# TMP102_Breakout-v12.net
KiCad netlist of a schematic drawn in EAGLE
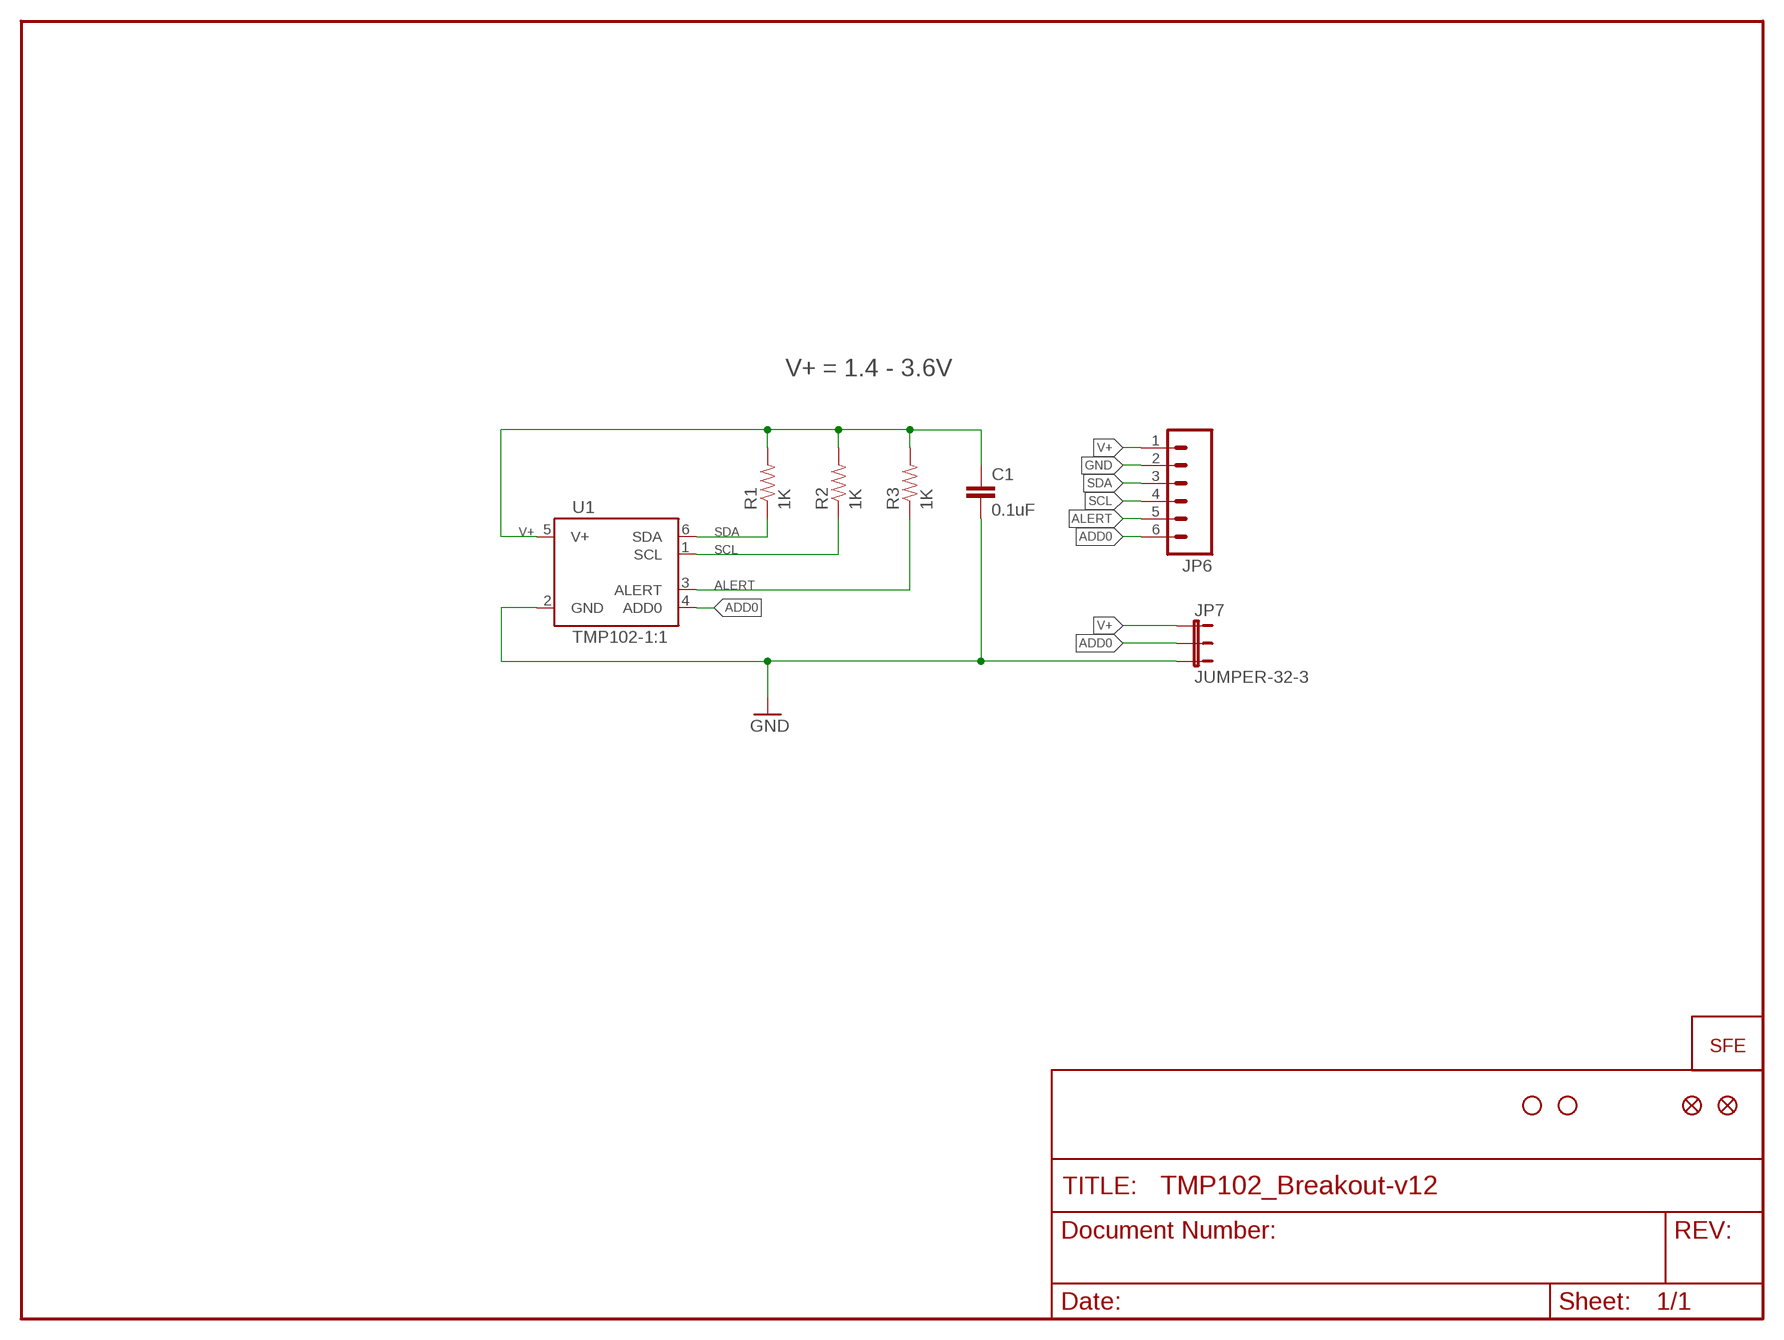
[diagram p0: schematic, sheet 1]

(export (version "E")
  (design (tool "Eeschema 10.0.6"))
  (components
    (comp (ref "C1")
      (value "0.1uF")
      (footprint "eagle-import:0603-CAP")
      (libsource (lib "eagle-import") (part "CAP0603-CAP"))
    )
    (comp (ref "JP1")
      (value "STAND-OFFTIGHT")
      (footprint "eagle-import:STAND-OFF-TIGHT")
      (libsource (lib "eagle-import") (part "STAND-OFFTIGHT"))
    )
    (comp (ref "JP2")
      (value "STAND-OFFTIGHT")
      (footprint "eagle-import:STAND-OFF-TIGHT")
      (libsource (lib "eagle-import") (part "STAND-OFFTIGHT"))
    )
    (comp (ref "JP3")
      (value "LOGO-SFESK")
      (footprint "eagle-import:SFE-LOGO-FLAME")
      (libsource (lib "eagle-import") (part "LOGO-SFESK"))
    )
    (comp (ref "JP4")
      (value "FIDUCIAL1X2")
      (footprint "eagle-import:FIDUCIAL-1X2")
      (libsource (lib "eagle-import") (part "FIDUCIAL1X2"))
    )
    (comp (ref "JP5")
      (value "FIDUCIAL1X2")
      (footprint "eagle-import:FIDUCIAL-1X2")
      (libsource (lib "eagle-import") (part "FIDUCIAL1X2"))
    )
    (comp (ref "JP6")
      (value "M06SIP")
      (footprint "eagle-import:1X06")
      (libsource (lib "eagle-import") (part "M06SIP"))
    )
    (comp (ref "JP7")
      (value "JUMPER-32-3")
      (footprint "eagle-import:SJ_3_PASTE2&3")
      (libsource (lib "eagle-import") (part "JUMPER-32-3"))
    )
    (comp (ref "R1")
      (value "1K")
      (footprint "eagle-import:0603-RES")
      (libsource (lib "eagle-import") (part "RESISTOR0603-RES"))
    )
    (comp (ref "R2")
      (value "1K")
      (footprint "eagle-import:0603-RES")
      (libsource (lib "eagle-import") (part "RESISTOR0603-RES"))
    )
    (comp (ref "R3")
      (value "1K")
      (footprint "eagle-import:0603-RES")
      (libsource (lib "eagle-import") (part "RESISTOR0603-RES"))
    )
    (comp (ref "U1")
      (value "TMP102-1:1")
      (footprint "eagle-import:SOT563-2")
      (libsource (lib "eagle-import") (part "TMP102-1{colon}1"))
    )
  )
  (nets
    (net (code "1") (name "ADD0") (class "Default")
      (node (ref "JP6") (pin "6") (pinfunction "6_6") (pintype "passive"))
      (node (ref "JP7") (pin "2") (pinfunction "2_2") (pintype "passive"))
      (node (ref "U1") (pin "4") (pinfunction "ADD0_4") (pintype "bidirectional"))
    )
    (net (code "2") (name "ALERT") (class "Default")
      (node (ref "JP6") (pin "5") (pinfunction "5_5") (pintype "passive"))
      (node (ref "R3") (pin "1") (pinfunction "1_1") (pintype "passive"))
      (node (ref "U1") (pin "3") (pinfunction "ALERT_3") (pintype "bidirectional"))
    )
    (net (code "3") (name "GND") (class "Default")
      (node (ref "C1") (pin "2") (pinfunction "2_2") (pintype "passive"))
      (node (ref "JP6") (pin "2") (pinfunction "2_2") (pintype "passive"))
      (node (ref "JP7") (pin "3") (pinfunction "3_3") (pintype "passive"))
      (node (ref "U1") (pin "2") (pinfunction "GND_2") (pintype "bidirectional"))
    )
    (net (code "4") (name "SCL") (class "Default")
      (node (ref "JP6") (pin "4") (pinfunction "4_4") (pintype "passive"))
      (node (ref "R2") (pin "1") (pinfunction "1_1") (pintype "passive"))
      (node (ref "U1") (pin "1") (pinfunction "SCL_1") (pintype "bidirectional"))
    )
    (net (code "5") (name "SDA") (class "Default")
      (node (ref "JP6") (pin "3") (pinfunction "3_3") (pintype "passive"))
      (node (ref "R1") (pin "1") (pinfunction "1_1") (pintype "passive"))
      (node (ref "U1") (pin "6") (pinfunction "SDA_6") (pintype "bidirectional"))
    )
    (net (code "6") (name "V+") (class "Default")
      (node (ref "C1") (pin "1") (pinfunction "1_1") (pintype "passive"))
      (node (ref "JP6") (pin "1") (pinfunction "1_1") (pintype "passive"))
      (node (ref "JP7") (pin "1") (pinfunction "1_1") (pintype "passive"))
      (node (ref "R1") (pin "2") (pinfunction "2_2") (pintype "passive"))
      (node (ref "R2") (pin "2") (pinfunction "2_2") (pintype "passive"))
      (node (ref "R3") (pin "2") (pinfunction "2_2") (pintype "passive"))
      (node (ref "U1") (pin "5") (pinfunction "V+_5") (pintype "bidirectional"))
    )
  )
)
